# SparkFun_RN-52_Breakout.net
KiCad netlist of a schematic drawn in EAGLE
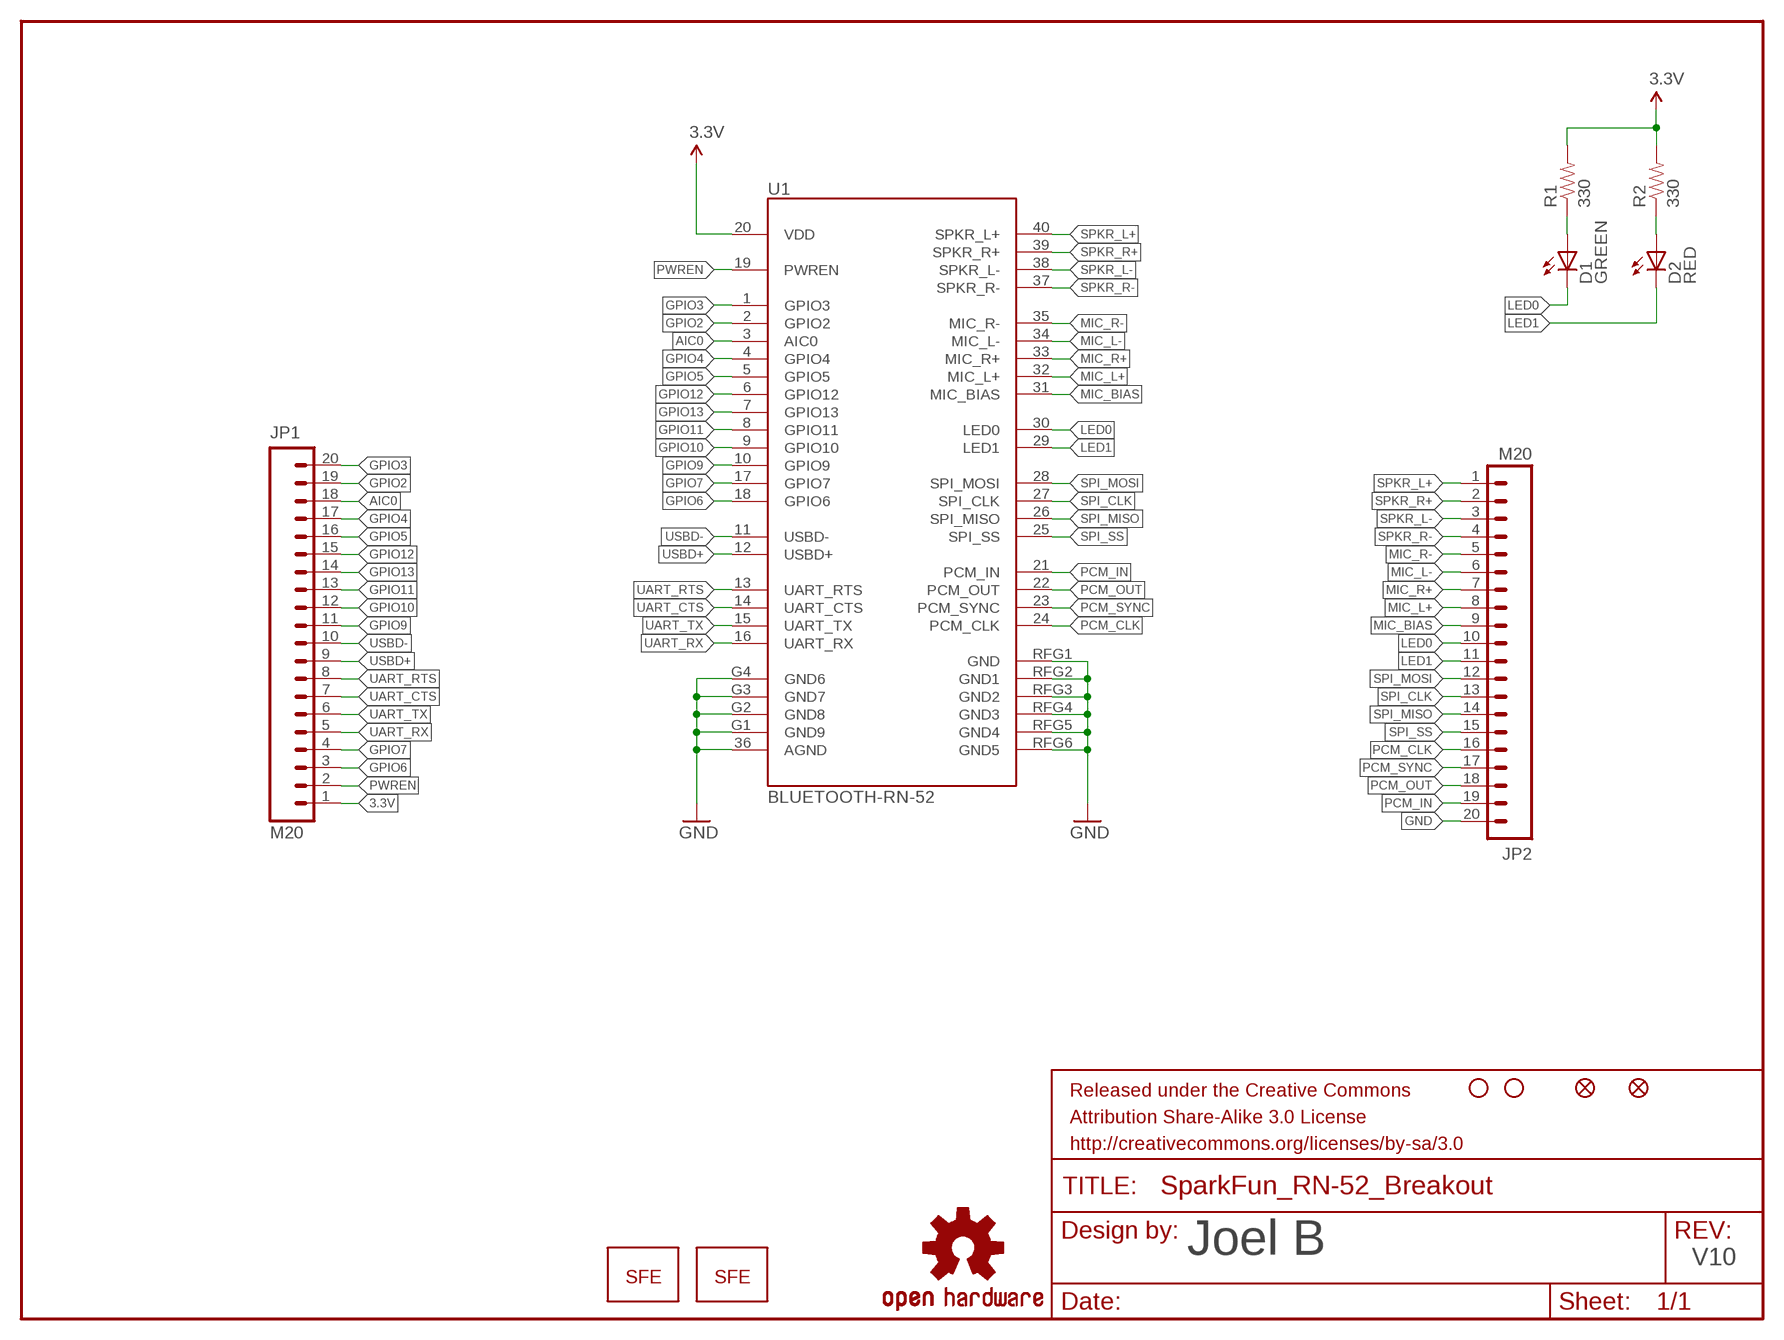
[diagram p0: schematic, sheet 1]

(export (version "E")
  (design (tool "Eeschema 10.0.6"))
  (components
    (comp (ref "D1")
      (value "GREEN")
      (footprint "eagle-import:LED-0603")
      (libsource (lib "eagle-import") (part "LED-GREEN0603"))
    )
    (comp (ref "D2")
      (value "RED")
      (footprint "eagle-import:LED-0603")
      (libsource (lib "eagle-import") (part "LED-RED0603"))
    )
    (comp (ref "FID1")
      (value "FIDUCIAL1X2")
      (footprint "eagle-import:FIDUCIAL-1X2")
      (libsource (lib "eagle-import") (part "FIDUCIAL1X2"))
    )
    (comp (ref "FID2")
      (value "FIDUCIAL1X2")
      (footprint "eagle-import:FIDUCIAL-1X2")
      (libsource (lib "eagle-import") (part "FIDUCIAL1X2"))
    )
    (comp (ref "FRAME1")
      (value "FRAME-LETTER")
      (footprint "eagle-import:CREATIVE_COMMONS")
      (libsource (lib "eagle-import") (part "FRAME-LETTER"))
    )
    (comp (ref "JP1")
      (value "M20")
      (footprint "eagle-import:1X20")
      (libsource (lib "eagle-import") (part "M20"))
    )
    (comp (ref "JP2")
      (value "M20")
      (footprint "eagle-import:1X20")
      (libsource (lib "eagle-import") (part "M20"))
    )
    (comp (ref "LOGO1")
      (value "OSHW-LOGOS")
      (footprint "eagle-import:OSHW-LOGO-S")
      (libsource (lib "eagle-import") (part "OSHW-LOGOS"))
    )
    (comp (ref "LOGO3")
      (value "LOGO-SFENEW")
      (footprint "eagle-import:SFE-NEW-WEBLOGO")
      (libsource (lib "eagle-import") (part "LOGO-SFENEW"))
    )
    (comp (ref "LOGO4")
      (value "LOGO-SFENW2")
      (footprint "eagle-import:SFE-NEW-WEB")
      (libsource (lib "eagle-import") (part "LOGO-SFENW2"))
    )
    (comp (ref "R1")
      (value "330")
      (footprint "eagle-import:0603-RES")
      (libsource (lib "eagle-import") (part "RESISTOR0603-RES"))
    )
    (comp (ref "R2")
      (value "330")
      (footprint "eagle-import:0603-RES")
      (libsource (lib "eagle-import") (part "RESISTOR0603-RES"))
    )
    (comp (ref "STANDOFF1")
      (value "STAND-OFF")
      (footprint "eagle-import:STAND-OFF")
      (libsource (lib "eagle-import") (part "STAND-OFF"))
    )
    (comp (ref "STANDOFF2")
      (value "STAND-OFF")
      (footprint "eagle-import:STAND-OFF")
      (libsource (lib "eagle-import") (part "STAND-OFF"))
    )
    (comp (ref "U1")
      (value "BLUETOOTH-RN-52")
      (footprint "eagle-import:RN-52")
      (libsource (lib "eagle-import") (part "BLUETOOTH-RN-52"))
    )
  )
  (nets
    (net (code "1") (name "3.3V") (class "Default")
      (node (ref "JP1") (pin "1") (pinfunction "1_1") (pintype "passive"))
      (node (ref "R1") (pin "2") (pinfunction "2_2") (pintype "passive"))
      (node (ref "R2") (pin "2") (pinfunction "2_2") (pintype "passive"))
      (node (ref "U1") (pin "20") (pinfunction "VDD_20") (pintype "bidirectional"))
    )
    (net (code "2") (name "AIC0") (class "Default")
      (node (ref "JP1") (pin "18") (pinfunction "18_18") (pintype "passive"))
      (node (ref "U1") (pin "3") (pinfunction "AIC0_3") (pintype "bidirectional"))
    )
    (net (code "3") (name "GND") (class "Default")
      (node (ref "JP2") (pin "20") (pinfunction "20_20") (pintype "passive"))
      (node (ref "U1") (pin "36") (pinfunction "AGND_36") (pintype "bidirectional"))
      (node (ref "U1") (pin "G1") (pinfunction "GND9_G1") (pintype "bidirectional"))
      (node (ref "U1") (pin "G2") (pinfunction "GND8_G2") (pintype "bidirectional"))
      (node (ref "U1") (pin "G3") (pinfunction "GND7_G3") (pintype "bidirectional"))
      (node (ref "U1") (pin "G4") (pinfunction "GND6_G4") (pintype "bidirectional"))
      (node (ref "U1") (pin "RFG1") (pinfunction "GND_RFG1") (pintype "bidirectional"))
      (node (ref "U1") (pin "RFG2") (pinfunction "GND1_RFG2") (pintype "bidirectional"))
      (node (ref "U1") (pin "RFG3") (pinfunction "GND2_RFG3") (pintype "bidirectional"))
      (node (ref "U1") (pin "RFG4") (pinfunction "GND3_RFG4") (pintype "bidirectional"))
      (node (ref "U1") (pin "RFG5") (pinfunction "GND4_RFG5") (pintype "bidirectional"))
      (node (ref "U1") (pin "RFG6") (pinfunction "GND5_RFG6") (pintype "bidirectional"))
    )
    (net (code "4") (name "GPIO2") (class "Default")
      (node (ref "JP1") (pin "19") (pinfunction "19_19") (pintype "passive"))
      (node (ref "U1") (pin "2") (pinfunction "GPIO2_2") (pintype "bidirectional"))
    )
    (net (code "5") (name "GPIO3") (class "Default")
      (node (ref "JP1") (pin "20") (pinfunction "20_20") (pintype "passive"))
      (node (ref "U1") (pin "1") (pinfunction "GPIO3_1") (pintype "bidirectional"))
    )
    (net (code "6") (name "GPIO4") (class "Default")
      (node (ref "JP1") (pin "17") (pinfunction "17_17") (pintype "passive"))
      (node (ref "U1") (pin "4") (pinfunction "GPIO4_4") (pintype "bidirectional"))
    )
    (net (code "7") (name "GPIO5") (class "Default")
      (node (ref "JP1") (pin "16") (pinfunction "16_16") (pintype "passive"))
      (node (ref "U1") (pin "5") (pinfunction "GPIO5_5") (pintype "bidirectional"))
    )
    (net (code "8") (name "GPIO6") (class "Default")
      (node (ref "JP1") (pin "3") (pinfunction "3_3") (pintype "passive"))
      (node (ref "U1") (pin "18") (pinfunction "GPIO6_18") (pintype "bidirectional"))
    )
    (net (code "9") (name "GPIO7") (class "Default")
      (node (ref "JP1") (pin "4") (pinfunction "4_4") (pintype "passive"))
      (node (ref "U1") (pin "17") (pinfunction "GPIO7_17") (pintype "bidirectional"))
    )
    (net (code "10") (name "GPIO9") (class "Default")
      (node (ref "JP1") (pin "11") (pinfunction "11_11") (pintype "passive"))
      (node (ref "U1") (pin "10") (pinfunction "GPIO9_10") (pintype "bidirectional"))
    )
    (net (code "11") (name "GPIO10") (class "Default")
      (node (ref "JP1") (pin "12") (pinfunction "12_12") (pintype "passive"))
      (node (ref "U1") (pin "9") (pinfunction "GPIO10_9") (pintype "bidirectional"))
    )
    (net (code "12") (name "GPIO11") (class "Default")
      (node (ref "JP1") (pin "13") (pinfunction "13_13") (pintype "passive"))
      (node (ref "U1") (pin "8") (pinfunction "GPIO11_8") (pintype "bidirectional"))
    )
    (net (code "13") (name "GPIO12") (class "Default")
      (node (ref "JP1") (pin "15") (pinfunction "15_15") (pintype "passive"))
      (node (ref "U1") (pin "6") (pinfunction "GPIO12_6") (pintype "bidirectional"))
    )
    (net (code "14") (name "GPIO13") (class "Default")
      (node (ref "JP1") (pin "14") (pinfunction "14_14") (pintype "passive"))
      (node (ref "U1") (pin "7") (pinfunction "GPIO13_7") (pintype "bidirectional"))
    )
    (net (code "15") (name "LED0") (class "Default")
      (node (ref "D1") (pin "C") (pinfunction "C_C") (pintype "passive"))
      (node (ref "JP2") (pin "10") (pinfunction "10_10") (pintype "passive"))
      (node (ref "U1") (pin "30") (pinfunction "LED0_30") (pintype "bidirectional"))
    )
    (net (code "16") (name "LED1") (class "Default")
      (node (ref "D2") (pin "C") (pinfunction "C_C") (pintype "passive"))
      (node (ref "JP2") (pin "11") (pinfunction "11_11") (pintype "passive"))
      (node (ref "U1") (pin "29") (pinfunction "LED1_29") (pintype "bidirectional"))
    )
    (net (code "17") (name "MIC_BIAS") (class "Default")
      (node (ref "JP2") (pin "9") (pinfunction "9_9") (pintype "passive"))
      (node (ref "U1") (pin "31") (pinfunction "MIC_BIAS_31") (pintype "bidirectional"))
    )
    (net (code "18") (name "MIC_L+") (class "Default")
      (node (ref "JP2") (pin "8") (pinfunction "8_8") (pintype "passive"))
      (node (ref "U1") (pin "32") (pinfunction "MIC_L+_32") (pintype "bidirectional"))
    )
    (net (code "19") (name "MIC_L-") (class "Default")
      (node (ref "JP2") (pin "6") (pinfunction "6_6") (pintype "passive"))
      (node (ref "U1") (pin "34") (pinfunction "MIC_L-_34") (pintype "bidirectional"))
    )
    (net (code "20") (name "MIC_R+") (class "Default")
      (node (ref "JP2") (pin "7") (pinfunction "7_7") (pintype "passive"))
      (node (ref "U1") (pin "33") (pinfunction "MIC_R+_33") (pintype "bidirectional"))
    )
    (net (code "21") (name "MIC_R-") (class "Default")
      (node (ref "JP2") (pin "5") (pinfunction "5_5") (pintype "passive"))
      (node (ref "U1") (pin "35") (pinfunction "MIC_R-_35") (pintype "bidirectional"))
    )
    (net (code "22") (name "Net-(D1-PadA)") (class "Default")
      (node (ref "D1") (pin "A") (pinfunction "A_A") (pintype "passive"))
      (node (ref "R1") (pin "1") (pinfunction "1_1") (pintype "passive"))
    )
    (net (code "23") (name "Net-(D2-PadA)") (class "Default")
      (node (ref "D2") (pin "A") (pinfunction "A_A") (pintype "passive"))
      (node (ref "R2") (pin "1") (pinfunction "1_1") (pintype "passive"))
    )
    (net (code "24") (name "PCM_CLK") (class "Default")
      (node (ref "JP2") (pin "16") (pinfunction "16_16") (pintype "passive"))
      (node (ref "U1") (pin "24") (pinfunction "PCM_CLK_24") (pintype "bidirectional"))
    )
    (net (code "25") (name "PCM_IN") (class "Default")
      (node (ref "JP2") (pin "19") (pinfunction "19_19") (pintype "passive"))
      (node (ref "U1") (pin "21") (pinfunction "PCM_IN_21") (pintype "bidirectional"))
    )
    (net (code "26") (name "PCM_OUT") (class "Default")
      (node (ref "JP2") (pin "18") (pinfunction "18_18") (pintype "passive"))
      (node (ref "U1") (pin "22") (pinfunction "PCM_OUT_22") (pintype "bidirectional"))
    )
    (net (code "27") (name "PCM_SYNC") (class "Default")
      (node (ref "JP2") (pin "17") (pinfunction "17_17") (pintype "passive"))
      (node (ref "U1") (pin "23") (pinfunction "PCM_SYNC_23") (pintype "bidirectional"))
    )
    (net (code "28") (name "PWREN") (class "Default")
      (node (ref "JP1") (pin "2") (pinfunction "2_2") (pintype "passive"))
      (node (ref "U1") (pin "19") (pinfunction "PWREN_19") (pintype "bidirectional"))
    )
    (net (code "29") (name "SPI_CLK") (class "Default")
      (node (ref "JP2") (pin "13") (pinfunction "13_13") (pintype "passive"))
      (node (ref "U1") (pin "27") (pinfunction "SPI_CLK_27") (pintype "bidirectional"))
    )
    (net (code "30") (name "SPI_MISO") (class "Default")
      (node (ref "JP2") (pin "14") (pinfunction "14_14") (pintype "passive"))
      (node (ref "U1") (pin "26") (pinfunction "SPI_MISO_26") (pintype "bidirectional"))
    )
    (net (code "31") (name "SPI_MOSI") (class "Default")
      (node (ref "JP2") (pin "12") (pinfunction "12_12") (pintype "passive"))
      (node (ref "U1") (pin "28") (pinfunction "SPI_MOSI_28") (pintype "bidirectional"))
    )
    (net (code "32") (name "SPI_SS") (class "Default")
      (node (ref "JP2") (pin "15") (pinfunction "15_15") (pintype "passive"))
      (node (ref "U1") (pin "25") (pinfunction "SPI_SS_25") (pintype "bidirectional"))
    )
    (net (code "33") (name "SPKR_L+") (class "Default")
      (node (ref "JP2") (pin "1") (pinfunction "1_1") (pintype "passive"))
      (node (ref "U1") (pin "40") (pinfunction "SPKR_L+_40") (pintype "bidirectional"))
    )
    (net (code "34") (name "SPKR_L-") (class "Default")
      (node (ref "JP2") (pin "3") (pinfunction "3_3") (pintype "passive"))
      (node (ref "U1") (pin "38") (pinfunction "SPKR_L-_38") (pintype "bidirectional"))
    )
    (net (code "35") (name "SPKR_R+") (class "Default")
      (node (ref "JP2") (pin "2") (pinfunction "2_2") (pintype "passive"))
      (node (ref "U1") (pin "39") (pinfunction "SPKR_R+_39") (pintype "bidirectional"))
    )
    (net (code "36") (name "SPKR_R-") (class "Default")
      (node (ref "JP2") (pin "4") (pinfunction "4_4") (pintype "passive"))
      (node (ref "U1") (pin "37") (pinfunction "SPKR_R-_37") (pintype "bidirectional"))
    )
    (net (code "37") (name "UART_CTS") (class "Default")
      (node (ref "JP1") (pin "7") (pinfunction "7_7") (pintype "passive"))
      (node (ref "U1") (pin "14") (pinfunction "UART_CTS_14") (pintype "bidirectional"))
    )
    (net (code "38") (name "UART_RTS") (class "Default")
      (node (ref "JP1") (pin "8") (pinfunction "8_8") (pintype "passive"))
      (node (ref "U1") (pin "13") (pinfunction "UART_RTS_13") (pintype "bidirectional"))
    )
    (net (code "39") (name "UART_RX") (class "Default")
      (node (ref "JP1") (pin "5") (pinfunction "5_5") (pintype "passive"))
      (node (ref "U1") (pin "16") (pinfunction "UART_RX_16") (pintype "bidirectional"))
    )
    (net (code "40") (name "UART_TX") (class "Default")
      (node (ref "JP1") (pin "6") (pinfunction "6_6") (pintype "passive"))
      (node (ref "U1") (pin "15") (pinfunction "UART_TX_15") (pintype "bidirectional"))
    )
    (net (code "41") (name "USBD+") (class "Default")
      (node (ref "JP1") (pin "9") (pinfunction "9_9") (pintype "passive"))
      (node (ref "U1") (pin "12") (pinfunction "USBD+_12") (pintype "bidirectional"))
    )
    (net (code "42") (name "USBD-") (class "Default")
      (node (ref "JP1") (pin "10") (pinfunction "10_10") (pintype "passive"))
      (node (ref "U1") (pin "11") (pinfunction "USBD-_11") (pintype "bidirectional"))
    )
  )
)
